# brake-box.net
KiCad netlist of a schematic drawn in Altium Designer
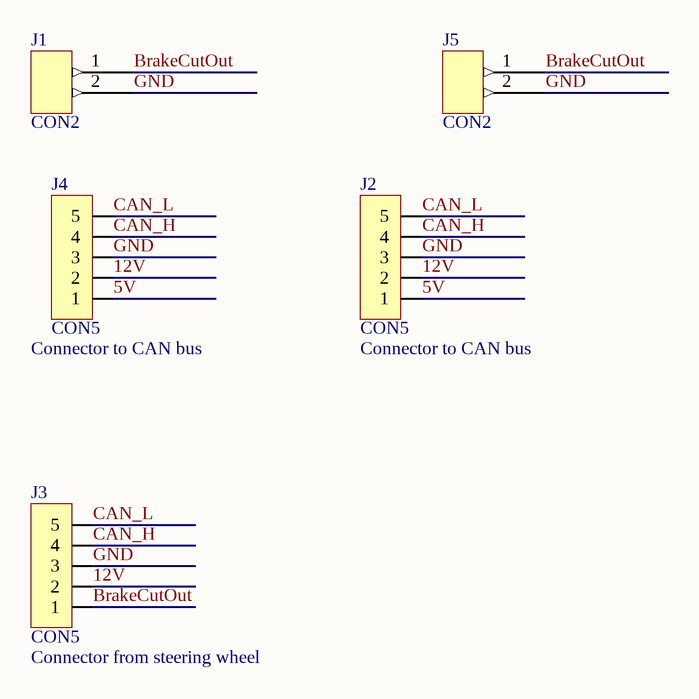
[diagram p0: brake-box.SchDoc]

(export (version "E")
  (design (tool "Eeschema 10.0.6"))
  (components
    (comp (ref "J1") (value "CON2") (footprint "MICROFIT-2") (libsource (lib "Connectors") (part "CON2")))
    (comp (ref "J2")
      (value "CON5")
      (footprint "TRIAD5F")
      (description "Connector")
      (libsource (lib "Connectors") (part "CON5"))
    )
    (comp (ref "J3")
      (value "CON5")
      (footprint "TRIAD5F")
      (description "Connector")
      (libsource (lib "Connectors") (part "CON5"))
    )
    (comp (ref "J4")
      (value "CON5")
      (footprint "TRIAD5F")
      (description "Connector")
      (libsource (lib "Connectors") (part "CON5"))
    )
    (comp (ref "J5") (value "CON2") (footprint "MICROFIT-2") (libsource (lib "Connectors") (part "CON2")))
  )
  (nets
    (net (code "1") (name "/5V") (class "Default")
      (node (ref "J2") (pin "1") (pinfunction "1_1") (pintype "passive"))
      (node (ref "J4") (pin "1") (pinfunction "1_1") (pintype "passive"))
    )
    (net (code "2") (name "/12V") (class "Default")
      (node (ref "J2") (pin "2") (pinfunction "2_2") (pintype "passive"))
      (node (ref "J3") (pin "2") (pinfunction "2_2") (pintype "passive"))
      (node (ref "J4") (pin "2") (pinfunction "2_2") (pintype "passive"))
    )
    (net (code "3") (name "/BrakeCutOut") (class "Default")
      (node (ref "J1") (pin "1") (pinfunction "1_1") (pintype "output"))
      (node (ref "J3") (pin "1") (pinfunction "1_1") (pintype "passive"))
      (node (ref "J5") (pin "1") (pinfunction "1_1") (pintype "output"))
    )
    (net (code "4") (name "/CAN_H") (class "Default")
      (node (ref "J2") (pin "4") (pinfunction "4_4") (pintype "passive"))
      (node (ref "J3") (pin "4") (pinfunction "4_4") (pintype "passive"))
      (node (ref "J4") (pin "4") (pinfunction "4_4") (pintype "passive"))
    )
    (net (code "5") (name "/CAN_L") (class "Default")
      (node (ref "J2") (pin "5") (pinfunction "5_5") (pintype "passive"))
      (node (ref "J3") (pin "5") (pinfunction "5_5") (pintype "passive"))
      (node (ref "J4") (pin "5") (pinfunction "5_5") (pintype "passive"))
    )
    (net (code "6") (name "/GND") (class "Default")
      (node (ref "J1") (pin "2") (pinfunction "2_2") (pintype "output"))
      (node (ref "J2") (pin "3") (pinfunction "3_3") (pintype "passive"))
      (node (ref "J3") (pin "3") (pinfunction "3_3") (pintype "passive"))
      (node (ref "J4") (pin "3") (pinfunction "3_3") (pintype "passive"))
      (node (ref "J5") (pin "2") (pinfunction "2_2") (pintype "output"))
    )
  )
)
